# SCH_GM_Camera_Harness_-_10-pin_male_adap.net
KiCad netlist of a schematic drawn in EasyEDA
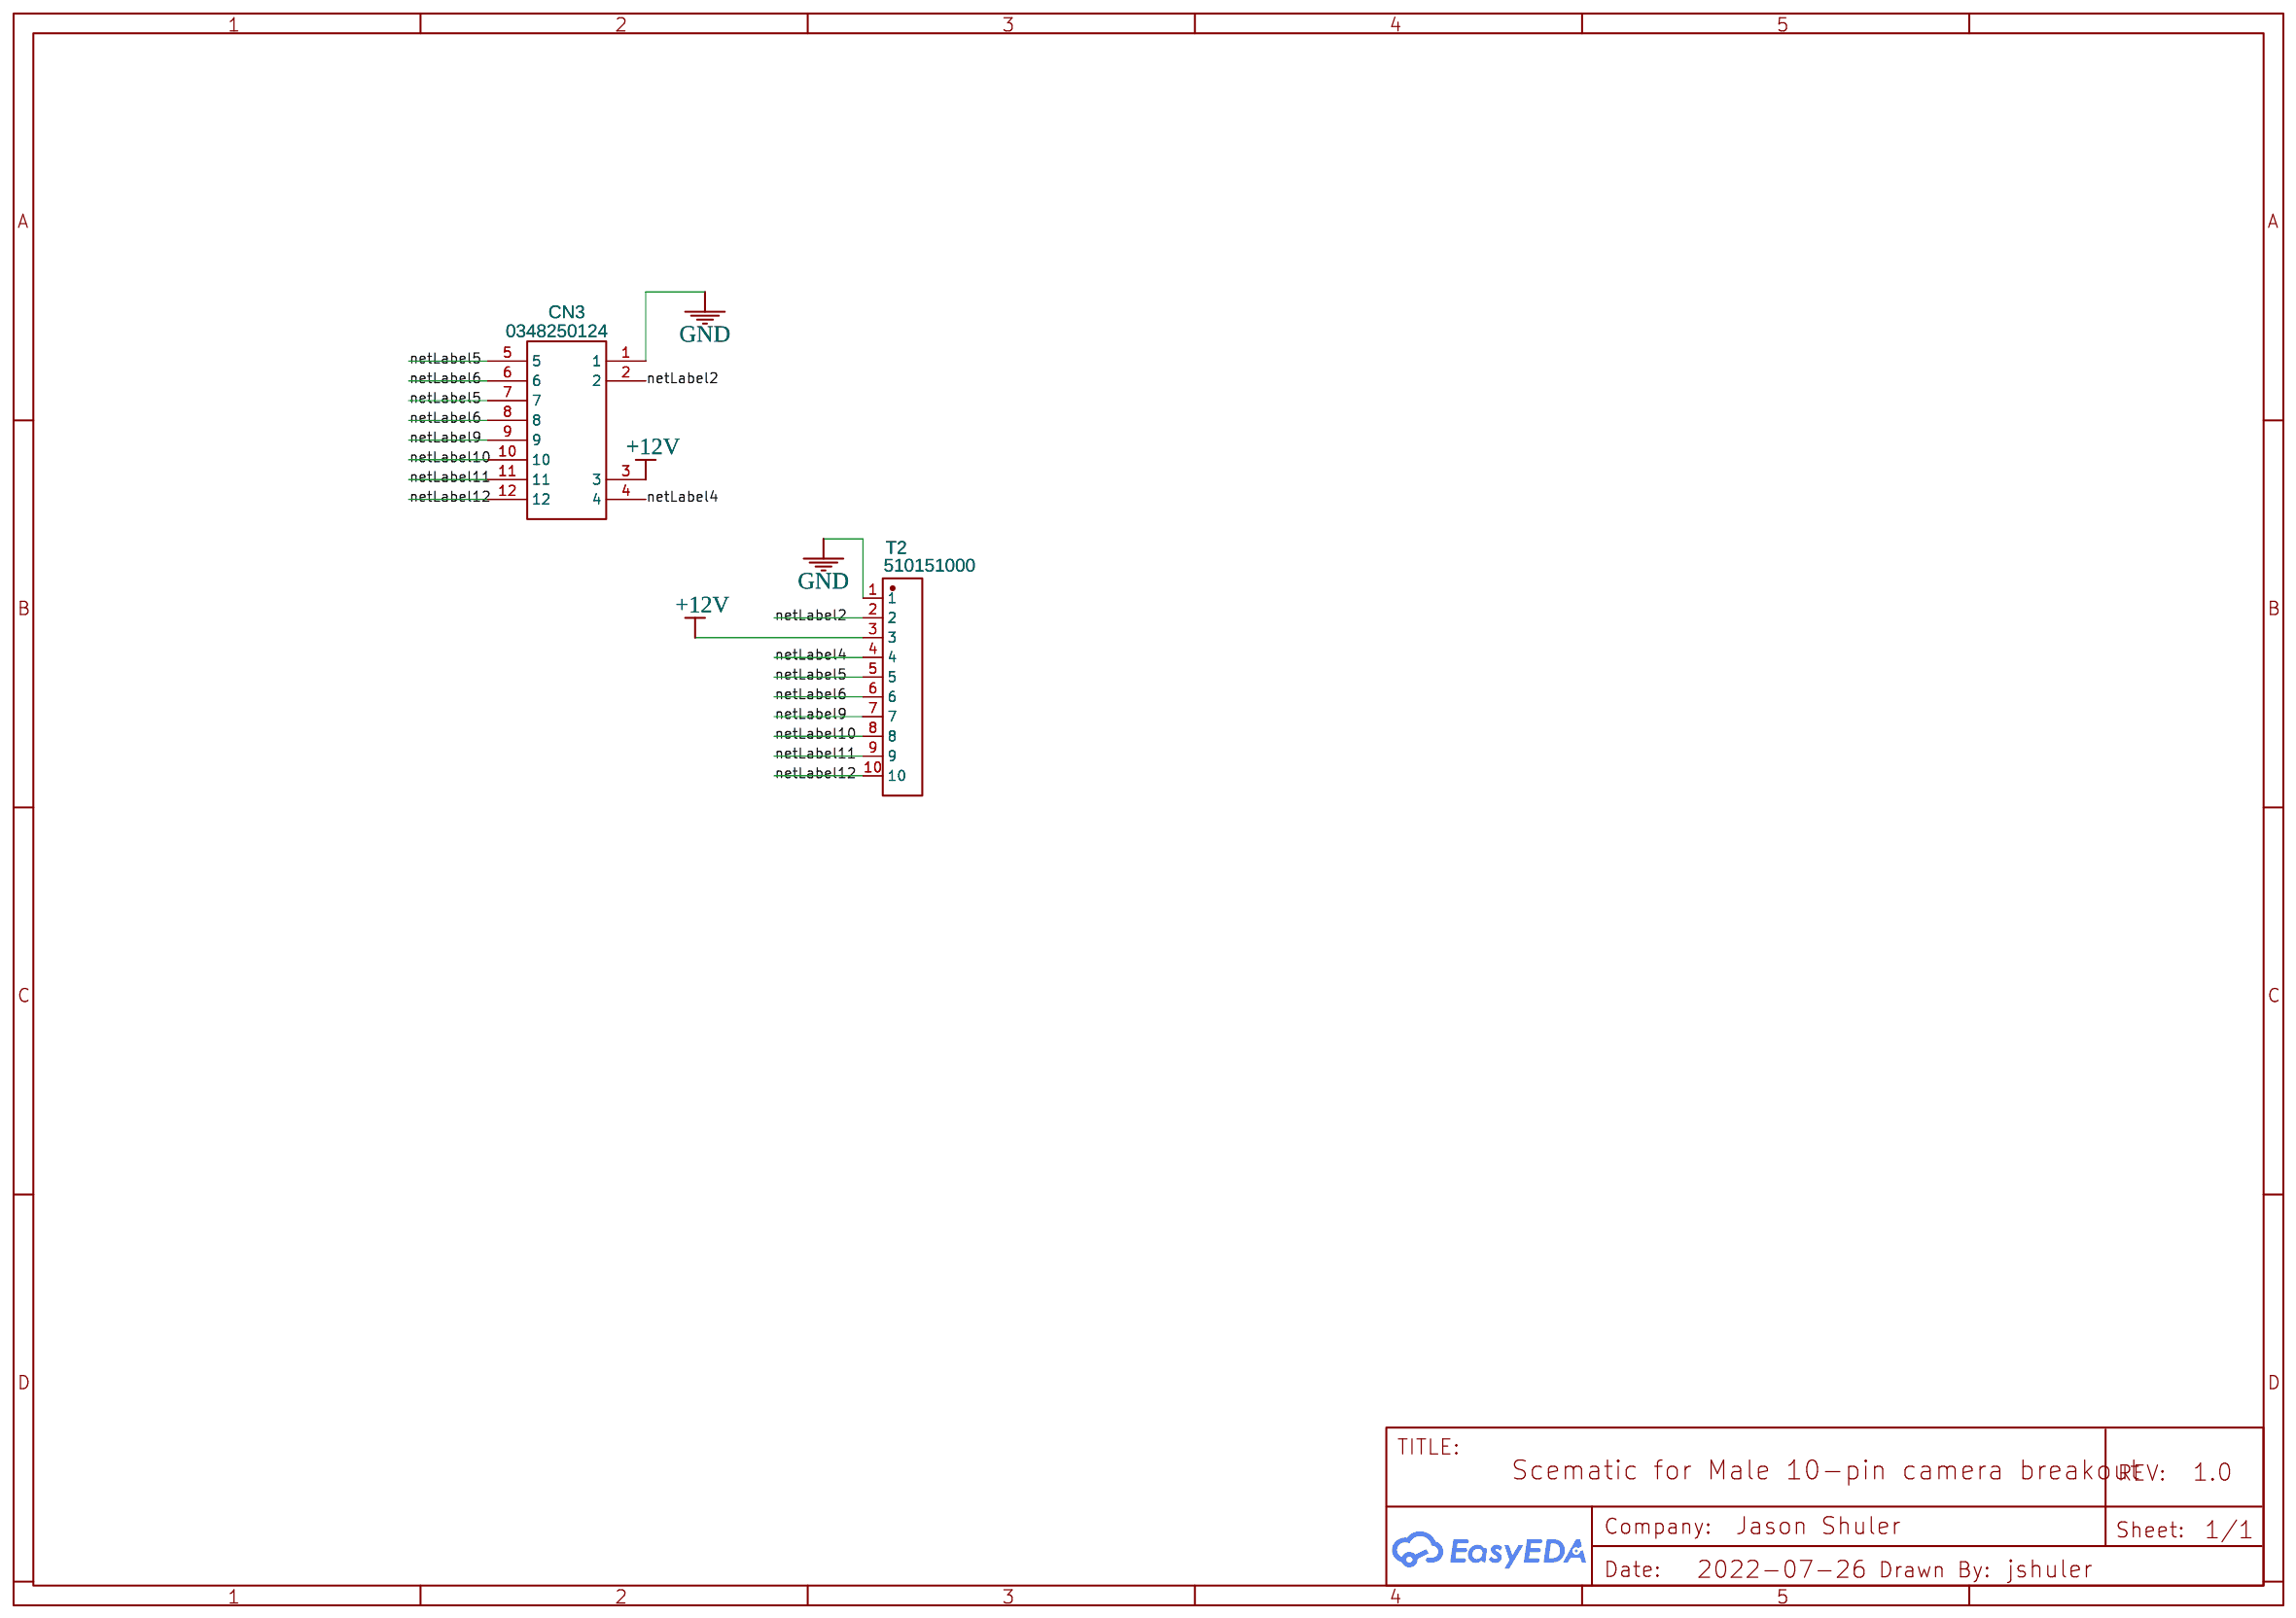
[diagram p0: schematic sheet]

(export (version "E")
  (design (tool "Eeschema 10.0.6"))
  (components
    (comp (ref "CN3")
      (value "0348250124")
      (fields (field (name "BOM_Supplier Part") "C122393"))
      (libsource (lib "") (part "0348250124"))
    )
    (comp (ref "T2") (value "510151000") (libsource (lib "") (part "510151000")))
  )
  (nets
    (net (code "1") (name "+12V") (class "Default")
      (node (ref "CN3") (pin "3") (pinfunction "3_3") (pintype "unspecified"))
      (node (ref "T2") (pin "3") (pinfunction "3_3") (pintype "unspecified"))
    )
    (net (code "2") (name "/netLabel2") (class "Default")
      (node (ref "CN3") (pin "2") (pinfunction "2_2") (pintype "unspecified"))
      (node (ref "T2") (pin "2") (pinfunction "2_2") (pintype "unspecified"))
    )
    (net (code "3") (name "/netLabel4") (class "Default")
      (node (ref "CN3") (pin "4") (pinfunction "4_4") (pintype "unspecified"))
      (node (ref "T2") (pin "4") (pinfunction "4_4") (pintype "unspecified"))
    )
    (net (code "4") (name "/netLabel5") (class "Default")
      (node (ref "CN3") (pin "5") (pinfunction "5_5") (pintype "unspecified"))
      (node (ref "CN3") (pin "7") (pinfunction "7_7") (pintype "unspecified"))
      (node (ref "T2") (pin "5") (pinfunction "5_5") (pintype "unspecified"))
    )
    (net (code "5") (name "/netLabel6") (class "Default")
      (node (ref "CN3") (pin "6") (pinfunction "6_6") (pintype "unspecified"))
      (node (ref "CN3") (pin "8") (pinfunction "8_8") (pintype "unspecified"))
      (node (ref "T2") (pin "6") (pinfunction "6_6") (pintype "unspecified"))
    )
    (net (code "6") (name "/netLabel9") (class "Default")
      (node (ref "CN3") (pin "9") (pinfunction "9_9") (pintype "unspecified"))
      (node (ref "T2") (pin "7") (pinfunction "7_7") (pintype "unspecified"))
    )
    (net (code "7") (name "/netLabel10") (class "Default")
      (node (ref "CN3") (pin "10") (pinfunction "10_10") (pintype "unspecified"))
      (node (ref "T2") (pin "8") (pinfunction "8_8") (pintype "unspecified"))
    )
    (net (code "8") (name "/netLabel11") (class "Default")
      (node (ref "CN3") (pin "11") (pinfunction "11_11") (pintype "unspecified"))
      (node (ref "T2") (pin "9") (pinfunction "9_9") (pintype "unspecified"))
    )
    (net (code "9") (name "/netLabel12") (class "Default")
      (node (ref "CN3") (pin "12") (pinfunction "12_12") (pintype "unspecified"))
      (node (ref "T2") (pin "10") (pinfunction "10_10") (pintype "unspecified"))
    )
    (net (code "10") (name "GND") (class "Default")
      (node (ref "CN3") (pin "1") (pinfunction "1_1") (pintype "unspecified"))
      (node (ref "T2") (pin "1") (pinfunction "1_1") (pintype "unspecified"))
    )
  )
)
